# pierce-test-board5.net
KiCad netlist of a schematic drawn in EAGLE
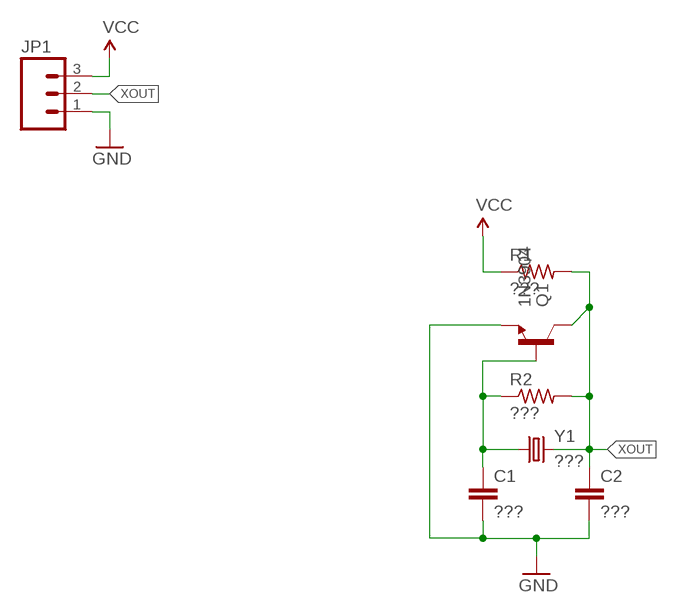
[diagram p0: schematic, sheet 1]

(export (version "E")
  (design (tool "Eeschema 10.0.6"))
  (components
    (comp (ref "C1")
      (value "???")
      (footprint "eagle-import:C025-024X044")
      (libsource (lib "eagle-import") (part "CAPACITOR-CERAMIC025-024X044"))
    )
    (comp (ref "C2")
      (value "???")
      (footprint "eagle-import:C025-024X044")
      (libsource (lib "eagle-import") (part "CAPACITOR-CERAMIC025-024X044"))
    )
    (comp (ref "JP1")
      (value "M03PTH")
      (footprint "eagle-import:1X03")
      (libsource (lib "eagle-import") (part "M03PTH"))
    )
    (comp (ref "Q1")
      (value "1N3904")
      (footprint "eagle-import:TO-92-AMMO")
      (libsource (lib "eagle-import") (part "TRANSISTOR_NPNTO-92-AMMO-EBC"))
    )
    (comp (ref "R1")
      (value "???")
      (footprint "eagle-import:RESISTOR-AXIAL-PTH-5.08MM")
      (libsource (lib "eagle-import") (part "RESISTORPTH-AXIAL-5.08MM"))
    )
    (comp (ref "R2")
      (value "???")
      (footprint "eagle-import:RESISTOR-AXIAL-PTH-5.08MM")
      (libsource (lib "eagle-import") (part "RESISTORPTH-AXIAL-5.08MM"))
    )
    (comp (ref "Y1")
      (value "???")
      (footprint "eagle-import:HC49U-V")
      (libsource (lib "eagle-import") (part "CRYSTALHC49UV"))
    )
  )
  (nets
    (net (code "1") (name "GND") (class "Default")
      (node (ref "C1") (pin "2") (pinfunction "2_2") (pintype "passive"))
      (node (ref "C2") (pin "2") (pinfunction "2_2") (pintype "passive"))
      (node (ref "JP1") (pin "1") (pinfunction "1_1") (pintype "passive"))
      (node (ref "Q1") (pin "1") (pinfunction "E_1") (pintype "passive"))
    )
    (net (code "2") (name "Net-(Q1-B)") (class "Default")
      (node (ref "C1") (pin "1") (pinfunction "1_1") (pintype "passive"))
      (node (ref "Q1") (pin "2") (pinfunction "B_2") (pintype "passive"))
      (node (ref "R2") (pin "P$1") (pinfunction "1_P$1") (pintype "passive"))
      (node (ref "Y1") (pin "1") (pinfunction "1_1") (pintype "passive"))
    )
    (net (code "3") (name "VCC") (class "Default")
      (node (ref "JP1") (pin "3") (pinfunction "3_3") (pintype "passive"))
      (node (ref "R1") (pin "P$1") (pinfunction "1_P$1") (pintype "passive"))
    )
    (net (code "4") (name "XOUT") (class "Default")
      (node (ref "C2") (pin "1") (pinfunction "1_1") (pintype "passive"))
      (node (ref "JP1") (pin "2") (pinfunction "2_2") (pintype "passive"))
      (node (ref "Q1") (pin "3") (pinfunction "C_3") (pintype "passive"))
      (node (ref "R1") (pin "P$2") (pinfunction "2_P$2") (pintype "passive"))
      (node (ref "R2") (pin "P$2") (pinfunction "2_P$2") (pintype "passive"))
      (node (ref "Y1") (pin "2") (pinfunction "2_2") (pintype "passive"))
    )
  )
)
